# Atom_Multiout_Addon_9p-Svid-Jack.net
KiCad netlist of a schematic drawn in EAGLE
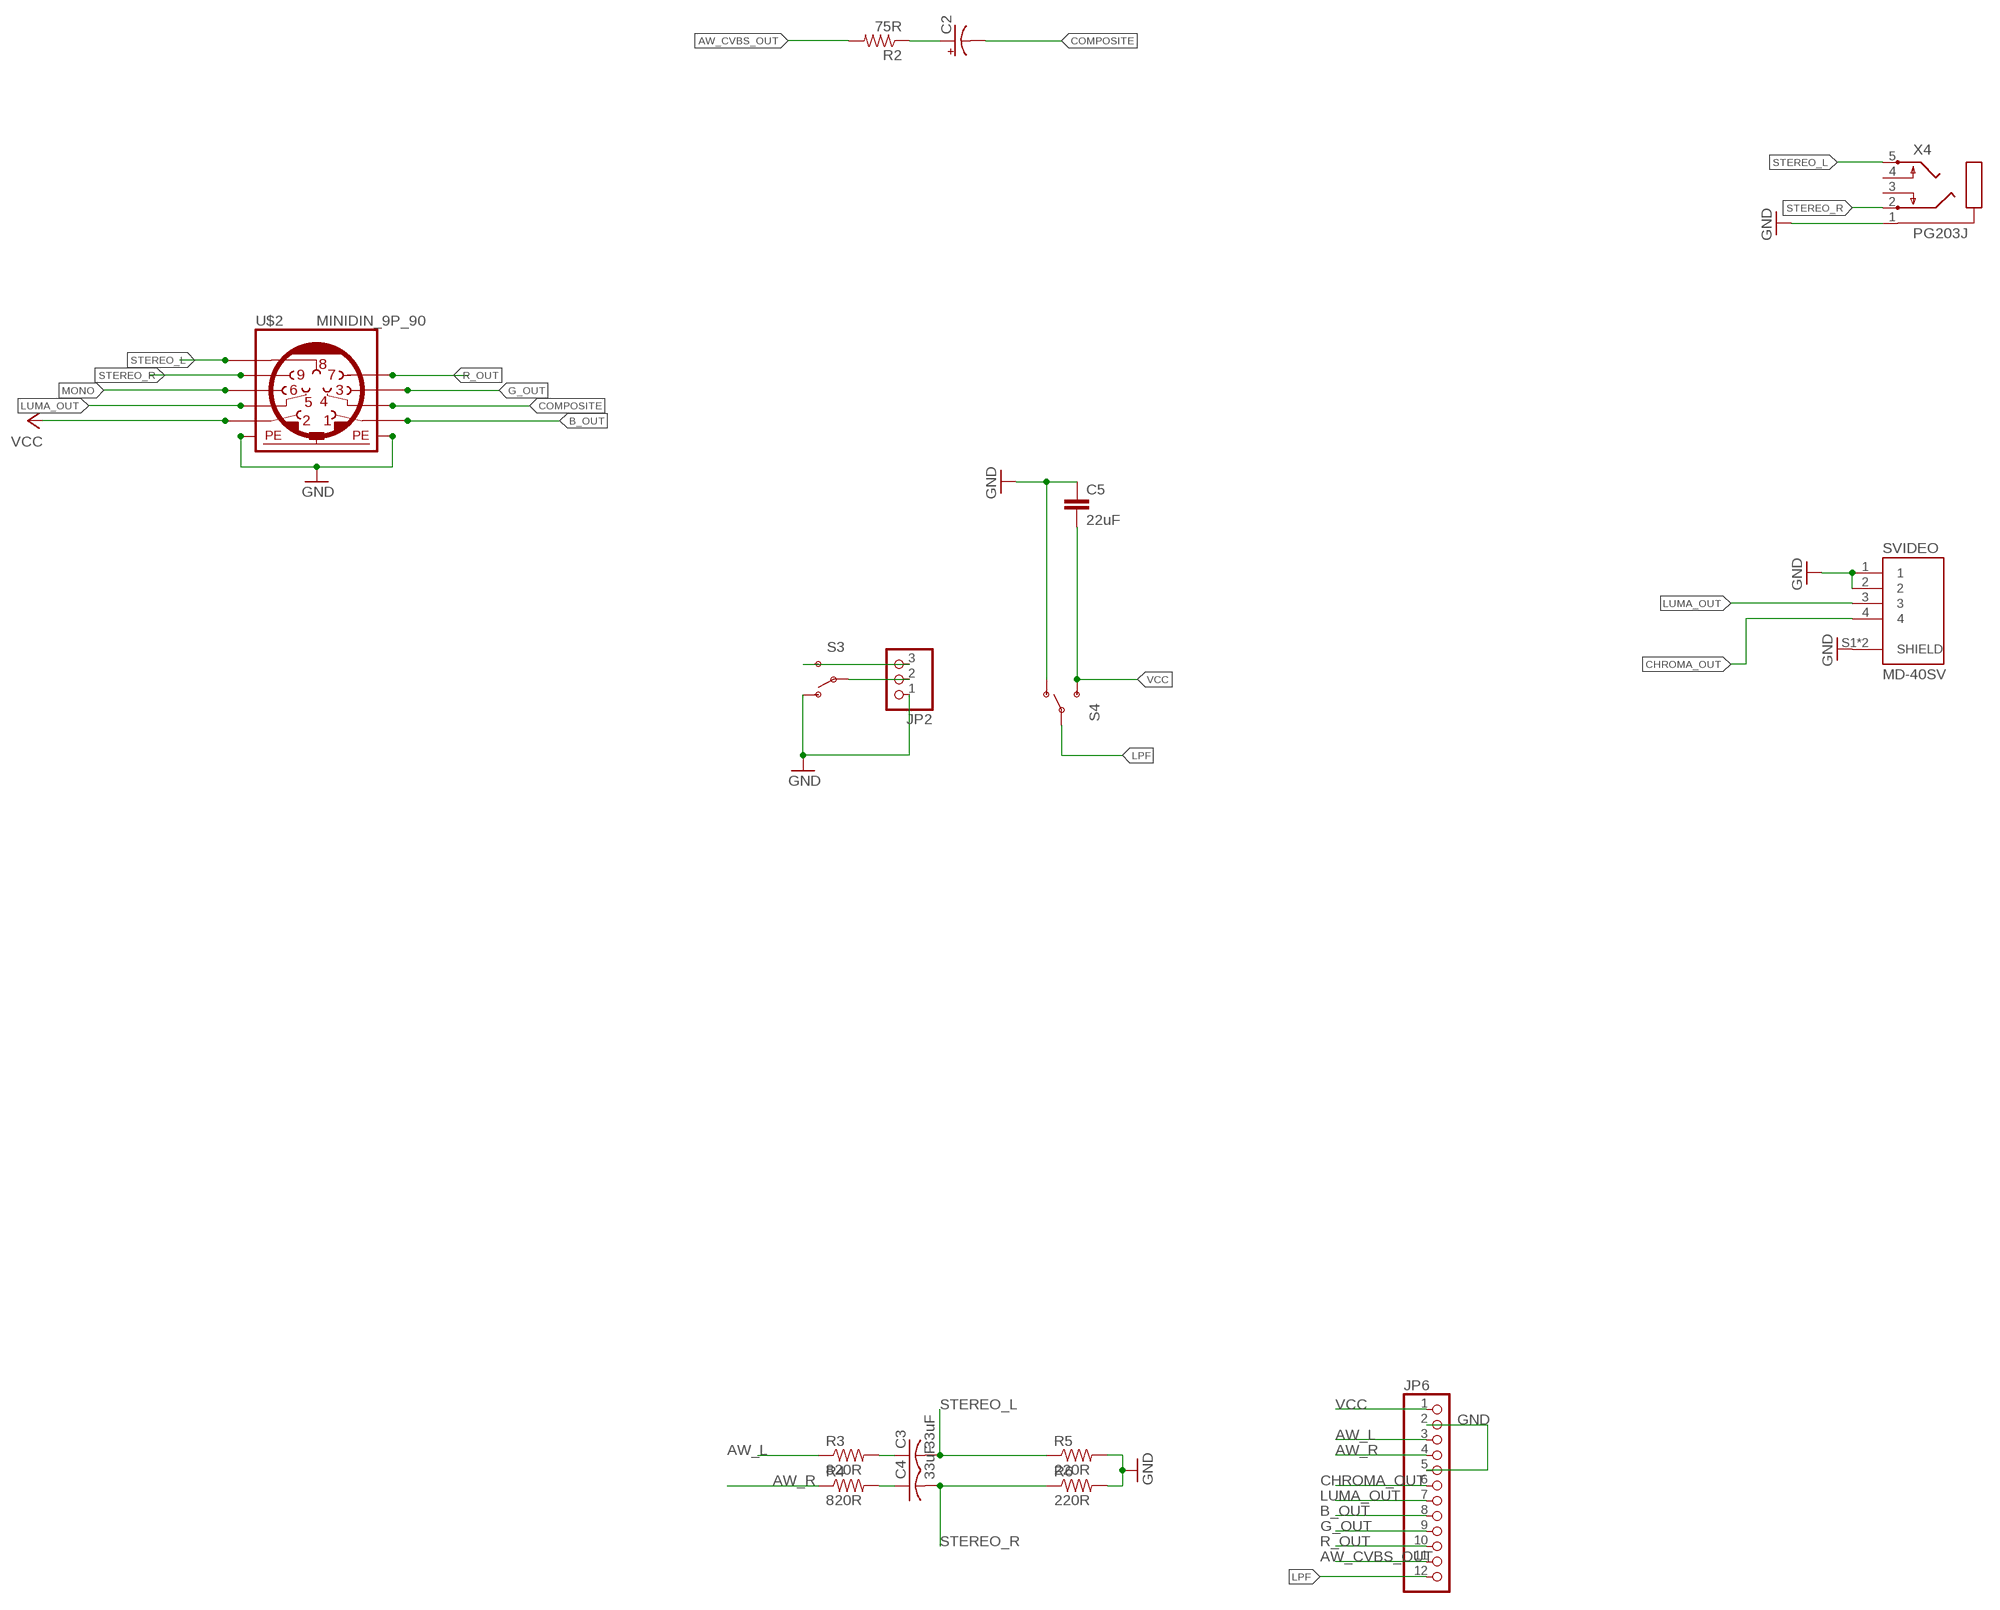
[diagram p0: schematic, sheet 1]

(export (version "E")
  (design (tool "Eeschema 10.0.6"))
  (components
    (comp (ref "C2")
      (value "CPOL-USD/7343-31W")
      (footprint "eagle-import:D_7343-31W")
      (libsource (lib "eagle-import") (part "CPOL-USD/7343-31W"))
    )
    (comp (ref "C3")
      (value "33uF")
      (footprint "eagle-import:C1206K")
      (libsource (lib "eagle-import") (part "C-USC1206K"))
    )
    (comp (ref "C4")
      (value "33uF")
      (footprint "eagle-import:C1206K")
      (libsource (lib "eagle-import") (part "C-USC1206K"))
    )
    (comp (ref "C5")
      (value "22uF")
      (footprint "eagle-import:C0603")
      (libsource (lib "eagle-import") (part "C-EUC0603"))
    )
    (comp (ref "JP2")
      (value "PINHD-1X03_2.54-S")
      (footprint "eagle-import:1X03-S")
      (libsource (lib "eagle-import") (part "PINHD-1X03_2.54-S"))
    )
    (comp (ref "JP6")
      (value "PINHD-1X12_2.54-S")
      (footprint "eagle-import:1X12-S")
      (libsource (lib "eagle-import") (part "PINHD-1X12_2.54-S"))
    )
    (comp (ref "R2")
      (value "75R")
      (footprint "eagle-import:R1206")
      (libsource (lib "eagle-import") (part "R-US_R1206"))
    )
    (comp (ref "R3")
      (value "820R")
      (footprint "eagle-import:R1206")
      (libsource (lib "eagle-import") (part "resistor_348_R-US_R1206"))
    )
    (comp (ref "R4")
      (value "820R")
      (footprint "eagle-import:R1206")
      (libsource (lib "eagle-import") (part "resistor_348_R-US_R1206"))
    )
    (comp (ref "R5")
      (value "220R")
      (footprint "eagle-import:R1206")
      (libsource (lib "eagle-import") (part "resistor_348_R-US_R1206"))
    )
    (comp (ref "R6")
      (value "220R")
      (footprint "eagle-import:R1206")
      (libsource (lib "eagle-import") (part "resistor_348_R-US_R1206"))
    )
    (comp (ref "S3")
      (value "SWITCH-SPDT-SMD-A")
      (footprint "eagle-import:SWITCH-SPST-SMD-A")
      (libsource (lib "eagle-import") (part "SWITCH-SPDT-SMD-A"))
    )
    (comp (ref "S4")
      (value "SWITCH-SPDT-SMD-A")
      (footprint "eagle-import:SWITCH-SPST-SMD-A")
      (libsource (lib "eagle-import") (part "SWITCH-SPDT-SMD-A"))
    )
    (comp (ref "SVIDEO")
      (value "MD-40SV")
      (footprint "eagle-import:CUI_MD-40SV")
      (fields (field (name "MF") "CUI Devices"))
      (libsource (lib "eagle-import") (part "MD-40SV"))
    )
    (comp (ref "U$2")
      (value "MINIDIN_9P_90")
      (footprint "eagle-import:MINIDIN9")
      (libsource (lib "eagle-import") (part "MINIDIN_9P_90"))
    )
    (comp (ref "X4")
      (value "PG203J")
      (footprint "eagle-import:PG203J")
      (libsource (lib "eagle-import") (part "PG203J"))
    )
  )
  (nets
    (net (code "1") (name "/AW_L") (class "Default")
      (node (ref "JP6") (pin "3") (pinfunction "3_3") (pintype "passive"))
      (node (ref "R3") (pin "1") (pinfunction "1_1") (pintype "passive"))
    )
    (net (code "2") (name "/AW_R") (class "Default")
      (node (ref "JP6") (pin "4") (pinfunction "4_4") (pintype "passive"))
      (node (ref "R4") (pin "1") (pinfunction "1_1") (pintype "passive"))
    )
    (net (code "3") (name "AW_CVBS_OUT") (class "Default")
      (node (ref "JP6") (pin "11") (pinfunction "11_11") (pintype "passive"))
      (node (ref "R2") (pin "2") (pinfunction "2_2") (pintype "passive"))
    )
    (net (code "4") (name "B_OUT") (class "Default")
      (node (ref "JP6") (pin "8") (pinfunction "8_8") (pintype "passive"))
      (node (ref "U$2") (pin "P$1") (pinfunction "1_P$1") (pintype "passive"))
    )
    (net (code "5") (name "CHROMA_OUT") (class "Default")
      (node (ref "JP6") (pin "6") (pinfunction "6_6") (pintype "passive"))
      (node (ref "SVIDEO") (pin "4") (pinfunction "4_4") (pintype "passive"))
    )
    (net (code "6") (name "COMPOSITE") (class "Default")
      (node (ref "C2") (pin "-") (pinfunction "-_-") (pintype "passive"))
      (node (ref "U$2") (pin "P$4") (pinfunction "4_P$4") (pintype "passive"))
    )
    (net (code "7") (name "GND") (class "Default")
      (node (ref "C5") (pin "1") (pinfunction "1_1") (pintype "passive"))
      (node (ref "JP2") (pin "1") (pinfunction "1_1") (pintype "passive"))
      (node (ref "JP6") (pin "2") (pinfunction "2_2") (pintype "passive"))
      (node (ref "JP6") (pin "5") (pinfunction "5_5") (pintype "passive"))
      (node (ref "R5") (pin "2") (pinfunction "2_2") (pintype "passive"))
      (node (ref "R6") (pin "2") (pinfunction "2_2") (pintype "passive"))
      (node (ref "S3") (pin "1") (pinfunction "O_1") (pintype "passive"))
      (node (ref "S4") (pin "1") (pinfunction "O_1") (pintype "passive"))
      (node (ref "SVIDEO") (pin "1") (pinfunction "1_1") (pintype "passive"))
      (node (ref "SVIDEO") (pin "2") (pinfunction "2_2") (pintype "passive"))
      (node (ref "SVIDEO") (pin "S1") (pinfunction "SHIELD_S1") (pintype "passive"))
      (node (ref "SVIDEO") (pin "S2") (pinfunction "SHIELD_S2") (pintype "passive"))
      (node (ref "U$2") (pin "P$10") (pinfunction "PE1_P$10") (pintype "power_in"))
      (node (ref "U$2") (pin "P$11") (pinfunction "PE3_P$11") (pintype "power_in"))
      (node (ref "X4") (pin "1") (pinfunction "1_1") (pintype "passive"))
    )
    (net (code "8") (name "G_OUT") (class "Default")
      (node (ref "JP6") (pin "9") (pinfunction "9_9") (pintype "passive"))
      (node (ref "U$2") (pin "P$3") (pinfunction "3_P$3") (pintype "passive"))
    )
    (net (code "9") (name "LPF") (class "Default")
      (node (ref "JP6") (pin "12") (pinfunction "12_12") (pintype "passive"))
      (node (ref "S4") (pin "2") (pinfunction "P_2") (pintype "passive"))
    )
    (net (code "10") (name "LUMA_OUT") (class "Default")
      (node (ref "JP6") (pin "7") (pinfunction "7_7") (pintype "passive"))
      (node (ref "SVIDEO") (pin "3") (pinfunction "3_3") (pintype "passive"))
      (node (ref "U$2") (pin "P$5") (pinfunction "5_P$5") (pintype "passive"))
    )
    (net (code "11") (name "MONO") (class "Default")
      (node (ref "U$2") (pin "P$6") (pinfunction "6_P$6") (pintype "passive"))
    )
    (net (code "12") (name "Net-(C2-Pad+)") (class "Default")
      (node (ref "C2") (pin "+") (pinfunction "+_+") (pintype "passive"))
      (node (ref "R2") (pin "1") (pinfunction "1_1") (pintype "passive"))
    )
    (net (code "13") (name "Net-(C3-Pad1)") (class "Default")
      (node (ref "C3") (pin "1") (pinfunction "1_1") (pintype "passive"))
      (node (ref "R3") (pin "2") (pinfunction "2_2") (pintype "passive"))
    )
    (net (code "14") (name "Net-(C4-Pad1)") (class "Default")
      (node (ref "C4") (pin "1") (pinfunction "1_1") (pintype "passive"))
      (node (ref "R4") (pin "2") (pinfunction "2_2") (pintype "passive"))
    )
    (net (code "15") (name "Net-(S3-P)") (class "Default")
      (node (ref "JP2") (pin "2") (pinfunction "2_2") (pintype "passive"))
      (node (ref "S3") (pin "2") (pinfunction "P_2") (pintype "passive"))
    )
    (net (code "16") (name "Net-(S3-S)") (class "Default")
      (node (ref "JP2") (pin "3") (pinfunction "3_3") (pintype "passive"))
      (node (ref "S3") (pin "3") (pinfunction "S_3") (pintype "passive"))
    )
    (net (code "17") (name "R_OUT") (class "Default")
      (node (ref "JP6") (pin "10") (pinfunction "10_10") (pintype "passive"))
      (node (ref "U$2") (pin "P$7") (pinfunction "7_P$7") (pintype "passive"))
    )
    (net (code "18") (name "STEREO_L") (class "Default")
      (node (ref "C3") (pin "2") (pinfunction "2_2") (pintype "passive"))
      (node (ref "R5") (pin "1") (pinfunction "1_1") (pintype "passive"))
      (node (ref "U$2") (pin "P$8") (pinfunction "8_P$8") (pintype "passive"))
      (node (ref "X4") (pin "5") (pinfunction "5_5") (pintype "passive"))
    )
    (net (code "19") (name "STEREO_R") (class "Default")
      (node (ref "C4") (pin "2") (pinfunction "2_2") (pintype "passive"))
      (node (ref "R6") (pin "1") (pinfunction "1_1") (pintype "passive"))
      (node (ref "U$2") (pin "P$9") (pinfunction "9_P$9") (pintype "passive"))
      (node (ref "X4") (pin "2") (pinfunction "2_2") (pintype "passive"))
    )
    (net (code "20") (name "VCC") (class "Default")
      (node (ref "C5") (pin "2") (pinfunction "2_2") (pintype "passive"))
      (node (ref "JP6") (pin "1") (pinfunction "1_1") (pintype "passive"))
      (node (ref "S4") (pin "3") (pinfunction "S_3") (pintype "passive"))
      (node (ref "U$2") (pin "P$2") (pinfunction "2_P$2") (pintype "passive"))
    )
    (net (code "21") (name "unconnected-(X4-Pad3)") (class "Default")
      (node (ref "X4") (pin "3") (pinfunction "3_3") (pintype "passive"))
    )
    (net (code "22") (name "unconnected-(X4-Pad4)") (class "Default")
      (node (ref "X4") (pin "4") (pinfunction "4_4") (pintype "passive"))
    )
  )
)
